# SplitUSB.net
KiCad netlist of a schematic drawn in EasyEDA Pro
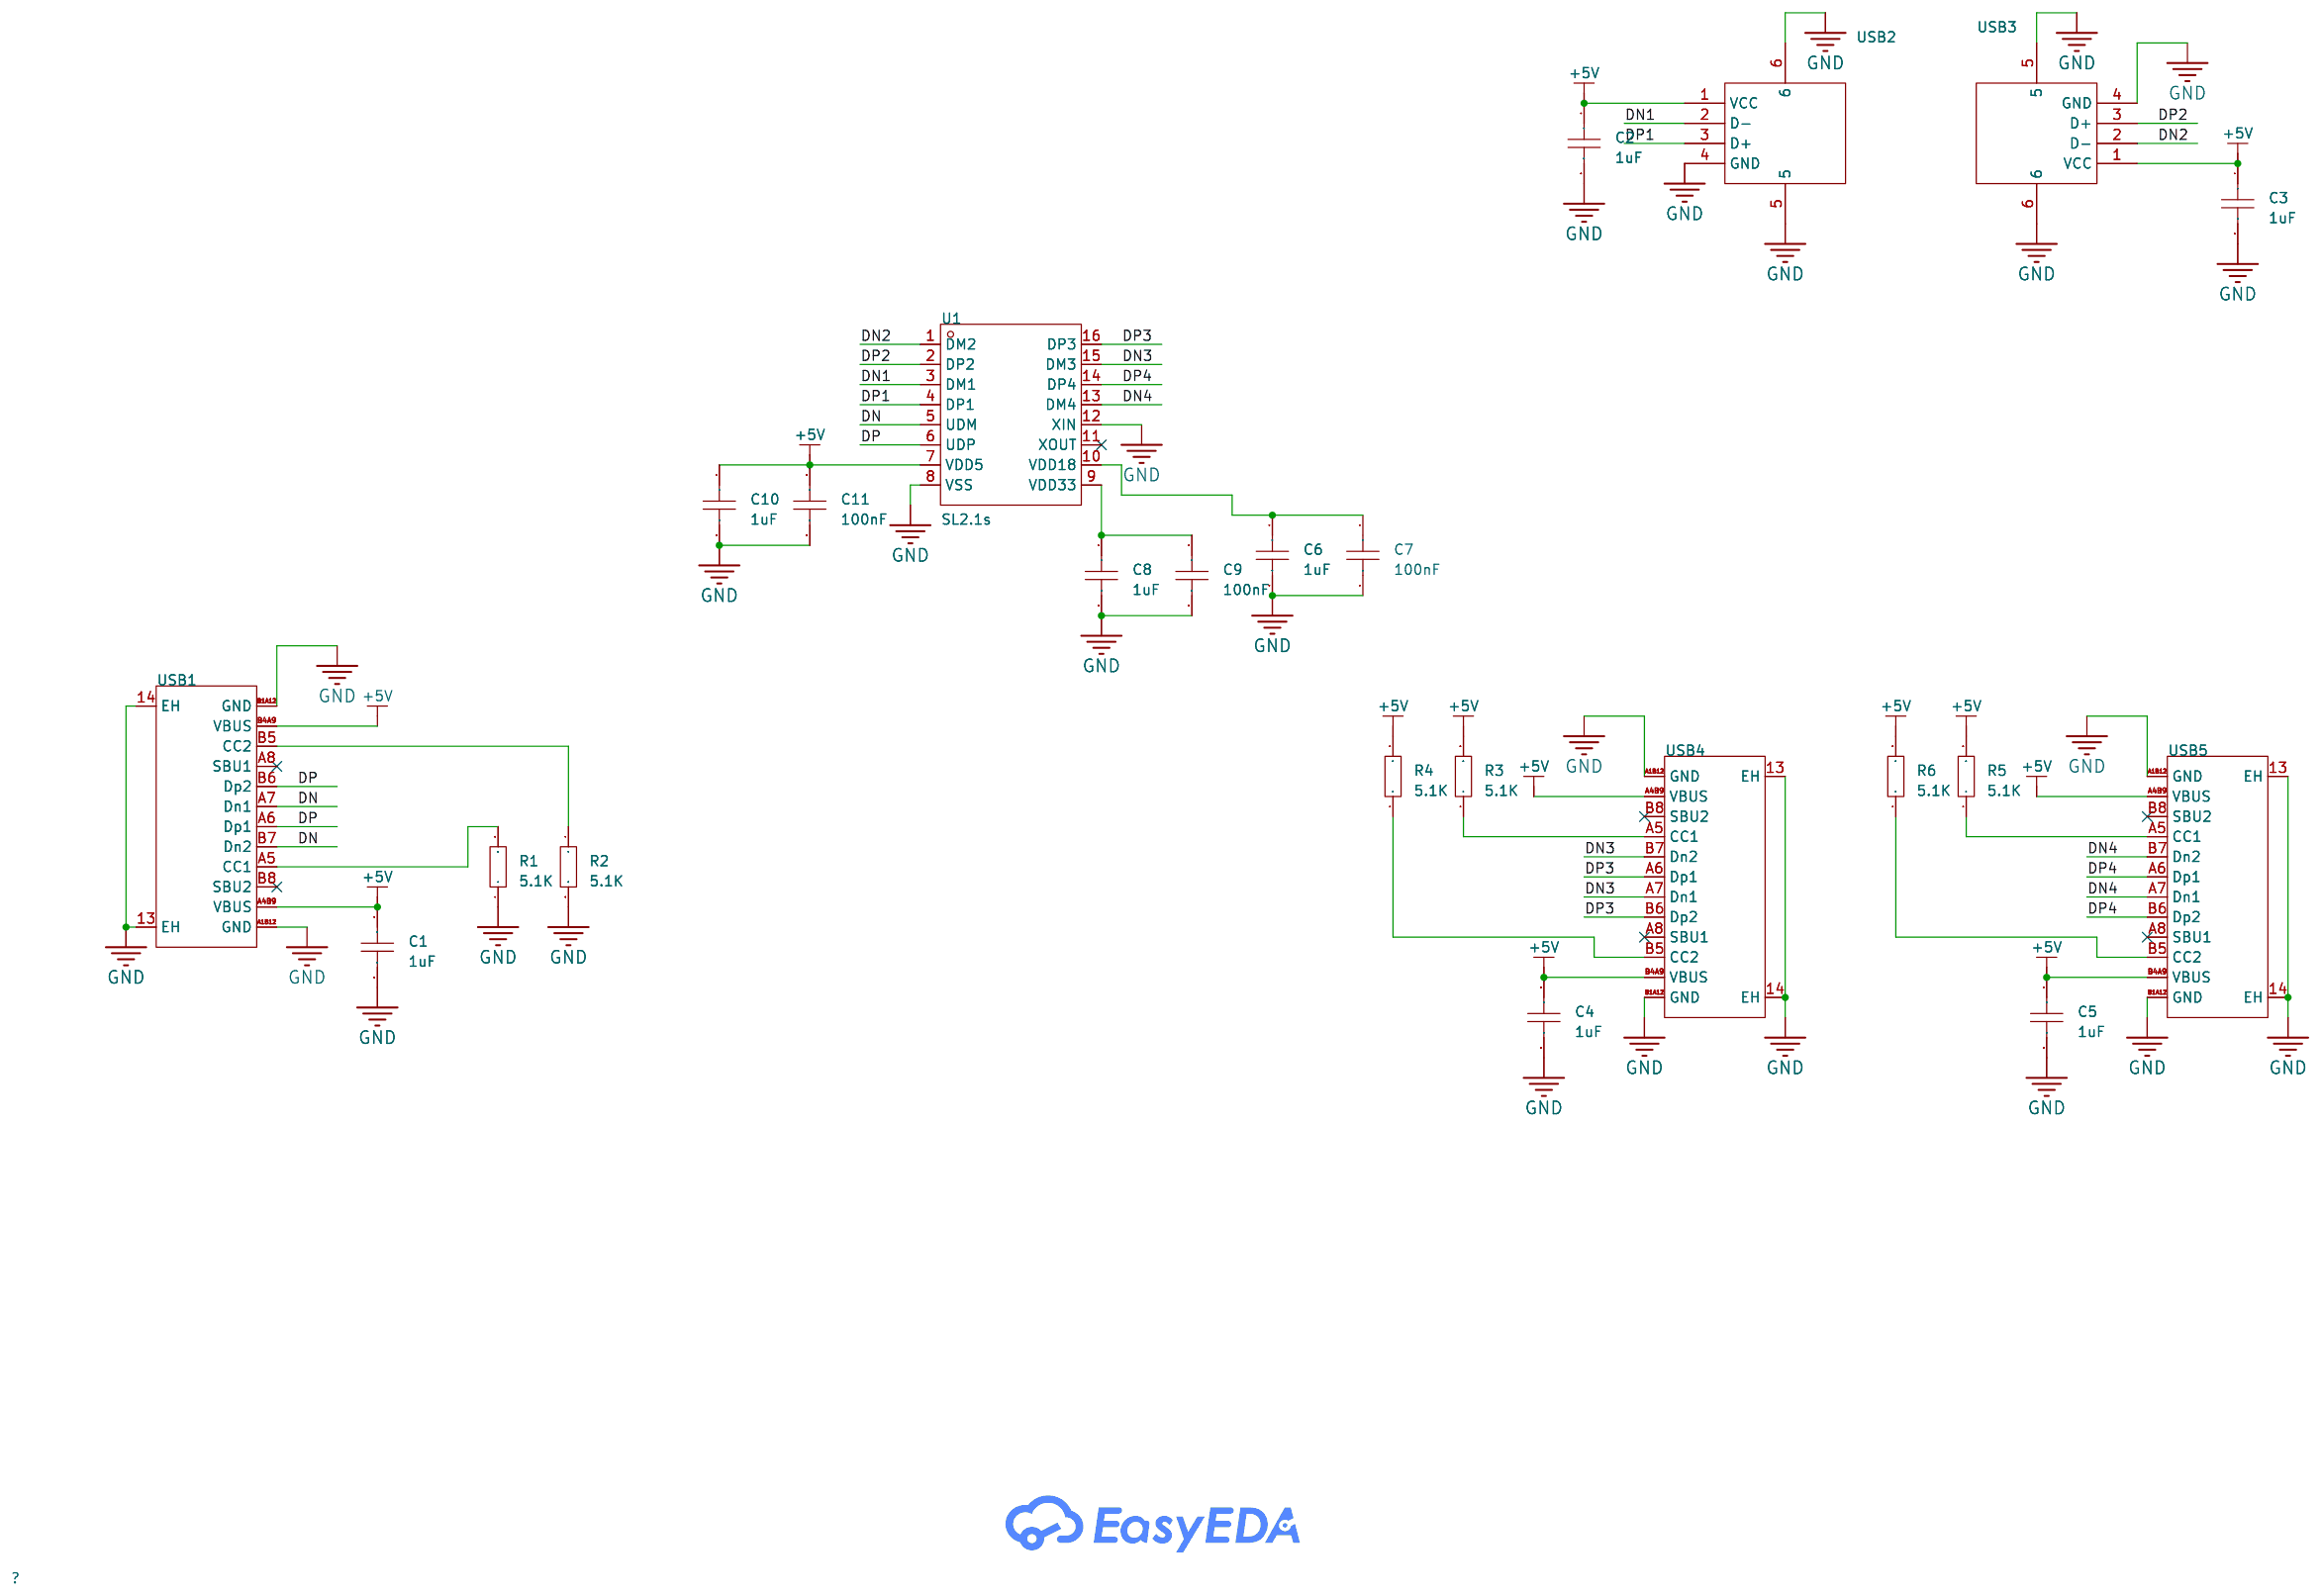
[diagram p0: schematic sheet]

(export (version "E")
  (design (tool "Eeschema 10.0.6"))
  (components
    (comp (ref "C1") (value "1uF") (footprint "easyedapro:C0603") (libsource (lib "easyedapro") (part "CAP")))
    (comp (ref "C2") (value "1uF") (footprint "easyedapro:C0603") (libsource (lib "easyedapro") (part "CAP")))
    (comp (ref "C3") (value "1uF") (footprint "easyedapro:C0603") (libsource (lib "easyedapro") (part "CAP")))
    (comp (ref "C4") (value "1uF") (footprint "easyedapro:C0603") (libsource (lib "easyedapro") (part "CAP")))
    (comp (ref "C5") (value "1uF") (footprint "easyedapro:C0603") (libsource (lib "easyedapro") (part "CAP")))
    (comp (ref "C6") (value "1uF") (footprint "easyedapro:C0603") (libsource (lib "easyedapro") (part "CAP")))
    (comp (ref "C7")
      (value "100nF")
      (footprint "easyedapro:C0603")
      (libsource (lib "easyedapro") (part "CAP"))
    )
    (comp (ref "C8") (value "1uF") (footprint "easyedapro:C0603") (libsource (lib "easyedapro") (part "CAP")))
    (comp (ref "C9")
      (value "100nF")
      (footprint "easyedapro:C0603")
      (libsource (lib "easyedapro") (part "CAP"))
    )
    (comp (ref "C10")
      (value "1uF")
      (footprint "easyedapro:C0603")
      (libsource (lib "easyedapro") (part "CAP"))
    )
    (comp (ref "C11")
      (value "100nF")
      (footprint "easyedapro:C0603")
      (libsource (lib "easyedapro") (part "CAP"))
    )
    (comp (ref "R1")
      (value "5.1K")
      (footprint "easyedapro:R0603")
      (libsource (lib "easyedapro") (part "Res"))
    )
    (comp (ref "R2")
      (value "5.1K")
      (footprint "easyedapro:R0603")
      (libsource (lib "easyedapro") (part "Res"))
    )
    (comp (ref "R3")
      (value "5.1K")
      (footprint "easyedapro:R0603")
      (libsource (lib "easyedapro") (part "Res"))
    )
    (comp (ref "R4")
      (value "5.1K")
      (footprint "easyedapro:R0603")
      (libsource (lib "easyedapro") (part "Res"))
    )
    (comp (ref "R5")
      (value "5.1K")
      (footprint "easyedapro:R0603")
      (libsource (lib "easyedapro") (part "Res"))
    )
    (comp (ref "R6")
      (value "5.1K")
      (footprint "easyedapro:R0603")
      (libsource (lib "easyedapro") (part "Res"))
    )
    (comp (ref "U1")
      (value "SL2.1s")
      (footprint "easyedapro:SSOP-16_L4.6-W2.6-P0.53-LS4.0-BL")
      (fields (field (name "Manufacturer") "CoreChips(和芯润德)"))
      (libsource (lib "easyedapro") (part "SL2.1S"))
    )
    (comp (ref "USB1")
      (value "TYPE-C 16PIN 2MD(073)")
      (footprint "easyedapro:USB-C-SMD_TYPE-C-16PIN-2MD-073")
      (fields (field (name "Manufacturer") "SHOU HAN(首韩)"))
      (libsource (lib "easyedapro") (part "TYPE-C 16PIN 2MD(073)"))
    )
    (comp (ref "USB2")
      (value "10.0 QHHTZB6.3")
      (footprint "easyedapro:USB-A-TH_10.0QHHTZB6.3")
      (fields (field (name "Manufacturer") "SHOU HAN(首韩)"))
      (libsource (lib "easyedapro") (part "10.0 QHHTZB6.3"))
    )
    (comp (ref "USB3")
      (value "10.0 QHHTZB6.3")
      (footprint "easyedapro:USB-A-TH_10.0QHHTZB6.3")
      (fields (field (name "Manufacturer") "SHOU HAN(首韩)"))
      (libsource (lib "easyedapro") (part "10.0 QHHTZB6.3"))
    )
    (comp (ref "USB4")
      (value "TYPE-C 16PIN 2MD(073)")
      (footprint "easyedapro:USB-C-SMD_TYPE-C-16PIN-2MD-073")
      (fields (field (name "Manufacturer") "SHOU HAN(首韩)"))
      (libsource (lib "easyedapro") (part "TYPE-C 16PIN 2MD(073)"))
    )
    (comp (ref "USB5")
      (value "TYPE-C 16PIN 2MD(073)")
      (footprint "easyedapro:USB-C-SMD_TYPE-C-16PIN-2MD-073")
      (fields (field (name "Manufacturer") "SHOU HAN(首韩)"))
      (libsource (lib "easyedapro") (part "TYPE-C 16PIN 2MD(073)"))
    )
  )
  (nets
    (net (code "1") (name "+5V") (class "Default")
      (node (ref "C1") (pin "1") (pinfunction "1_1") (pintype "input"))
      (node (ref "C10") (pin "1") (pinfunction "1_1") (pintype "input"))
      (node (ref "C11") (pin "1") (pinfunction "1_1") (pintype "input"))
      (node (ref "C2") (pin "1") (pinfunction "1_1") (pintype "input"))
      (node (ref "C3") (pin "1") (pinfunction "1_1") (pintype "input"))
      (node (ref "C4") (pin "1") (pinfunction "1_1") (pintype "input"))
      (node (ref "C5") (pin "1") (pinfunction "1_1") (pintype "input"))
      (node (ref "R3") (pin "2") (pinfunction "2_2") (pintype "input"))
      (node (ref "R4") (pin "2") (pinfunction "2_2") (pintype "input"))
      (node (ref "R5") (pin "2") (pinfunction "2_2") (pintype "input"))
      (node (ref "R6") (pin "2") (pinfunction "2_2") (pintype "input"))
      (node (ref "U1") (pin "7") (pinfunction "VDD5_7") (pintype "unspecified"))
      (node (ref "USB1") (pin "A4B9") (pinfunction "VBUS_A4B9") (pintype "unspecified"))
      (node (ref "USB1") (pin "B4A9") (pinfunction "VBUS_B4A9") (pintype "unspecified"))
      (node (ref "USB2") (pin "1") (pinfunction "VCC_1") (pintype "unspecified"))
      (node (ref "USB3") (pin "1") (pinfunction "VCC_1") (pintype "unspecified"))
      (node (ref "USB4") (pin "A4B9") (pinfunction "VBUS_A4B9") (pintype "unspecified"))
      (node (ref "USB4") (pin "B4A9") (pinfunction "VBUS_B4A9") (pintype "unspecified"))
      (node (ref "USB5") (pin "A4B9") (pinfunction "VBUS_A4B9") (pintype "unspecified"))
      (node (ref "USB5") (pin "B4A9") (pinfunction "VBUS_B4A9") (pintype "unspecified"))
    )
    (net (code "2") (name "/DN") (class "Default")
      (node (ref "U1") (pin "5") (pinfunction "UDM_5") (pintype "unspecified"))
      (node (ref "USB1") (pin "A7") (pinfunction "Dn1_A7") (pintype "unspecified"))
      (node (ref "USB1") (pin "B7") (pinfunction "Dn2_B7") (pintype "unspecified"))
    )
    (net (code "3") (name "/DN1") (class "Default")
      (node (ref "U1") (pin "3") (pinfunction "DM1_3") (pintype "unspecified"))
      (node (ref "USB2") (pin "2") (pinfunction "D-_2") (pintype "unspecified"))
    )
    (net (code "4") (name "/DN2") (class "Default")
      (node (ref "U1") (pin "1") (pinfunction "DM2_1") (pintype "unspecified"))
      (node (ref "USB3") (pin "2") (pinfunction "D-_2") (pintype "unspecified"))
    )
    (net (code "5") (name "/DN3") (class "Default")
      (node (ref "U1") (pin "15") (pinfunction "DM3_15") (pintype "unspecified"))
      (node (ref "USB4") (pin "A7") (pinfunction "Dn1_A7") (pintype "unspecified"))
      (node (ref "USB4") (pin "B7") (pinfunction "Dn2_B7") (pintype "unspecified"))
    )
    (net (code "6") (name "/DN4") (class "Default")
      (node (ref "U1") (pin "13") (pinfunction "DM4_13") (pintype "unspecified"))
      (node (ref "USB5") (pin "A7") (pinfunction "Dn1_A7") (pintype "unspecified"))
      (node (ref "USB5") (pin "B7") (pinfunction "Dn2_B7") (pintype "unspecified"))
    )
    (net (code "7") (name "/DP") (class "Default")
      (node (ref "U1") (pin "6") (pinfunction "UDP_6") (pintype "unspecified"))
      (node (ref "USB1") (pin "A6") (pinfunction "Dp1_A6") (pintype "unspecified"))
      (node (ref "USB1") (pin "B6") (pinfunction "Dp2_B6") (pintype "unspecified"))
    )
    (net (code "8") (name "/DP1") (class "Default")
      (node (ref "U1") (pin "4") (pinfunction "DP1_4") (pintype "unspecified"))
      (node (ref "USB2") (pin "3") (pinfunction "D+_3") (pintype "unspecified"))
    )
    (net (code "9") (name "/DP2") (class "Default")
      (node (ref "U1") (pin "2") (pinfunction "DP2_2") (pintype "unspecified"))
      (node (ref "USB3") (pin "3") (pinfunction "D+_3") (pintype "unspecified"))
    )
    (net (code "10") (name "/DP3") (class "Default")
      (node (ref "U1") (pin "16") (pinfunction "DP3_16") (pintype "unspecified"))
      (node (ref "USB4") (pin "A6") (pinfunction "Dp1_A6") (pintype "unspecified"))
      (node (ref "USB4") (pin "B6") (pinfunction "Dp2_B6") (pintype "unspecified"))
    )
    (net (code "11") (name "/DP4") (class "Default")
      (node (ref "U1") (pin "14") (pinfunction "DP4_14") (pintype "unspecified"))
      (node (ref "USB5") (pin "A6") (pinfunction "Dp1_A6") (pintype "unspecified"))
      (node (ref "USB5") (pin "B6") (pinfunction "Dp2_B6") (pintype "unspecified"))
    )
    (net (code "12") (name "GND") (class "Default")
      (node (ref "C1") (pin "2") (pinfunction "2_2") (pintype "input"))
      (node (ref "C10") (pin "2") (pinfunction "2_2") (pintype "input"))
      (node (ref "C11") (pin "2") (pinfunction "2_2") (pintype "input"))
      (node (ref "C2") (pin "2") (pinfunction "2_2") (pintype "input"))
      (node (ref "C3") (pin "2") (pinfunction "2_2") (pintype "input"))
      (node (ref "C4") (pin "2") (pinfunction "2_2") (pintype "input"))
      (node (ref "C5") (pin "2") (pinfunction "2_2") (pintype "input"))
      (node (ref "C6") (pin "2") (pinfunction "2_2") (pintype "input"))
      (node (ref "C7") (pin "2") (pinfunction "2_2") (pintype "input"))
      (node (ref "C8") (pin "2") (pinfunction "2_2") (pintype "input"))
      (node (ref "C9") (pin "2") (pinfunction "2_2") (pintype "input"))
      (node (ref "R1") (pin "1") (pinfunction "1_1") (pintype "input"))
      (node (ref "R2") (pin "2") (pinfunction "2_2") (pintype "input"))
      (node (ref "U1") (pin "12") (pinfunction "XIN_12") (pintype "unspecified"))
      (node (ref "U1") (pin "8") (pinfunction "VSS_8") (pintype "unspecified"))
      (node (ref "USB1") (pin "13") (pinfunction "EH_13") (pintype "unspecified"))
      (node (ref "USB1") (pin "14") (pinfunction "EH_14") (pintype "unspecified"))
      (node (ref "USB1") (pin "A1B12") (pinfunction "GND_A1B12") (pintype "unspecified"))
      (node (ref "USB1") (pin "B1A12") (pinfunction "GND_B1A12") (pintype "unspecified"))
      (node (ref "USB2") (pin "4") (pinfunction "GND_4") (pintype "unspecified"))
      (node (ref "USB2") (pin "5") (pinfunction "5_5") (pintype "unspecified"))
      (node (ref "USB2") (pin "6") (pinfunction "6_6") (pintype "unspecified"))
      (node (ref "USB3") (pin "4") (pinfunction "GND_4") (pintype "unspecified"))
      (node (ref "USB3") (pin "5") (pinfunction "5_5") (pintype "unspecified"))
      (node (ref "USB3") (pin "6") (pinfunction "6_6") (pintype "unspecified"))
      (node (ref "USB4") (pin "13") (pinfunction "EH_13") (pintype "unspecified"))
      (node (ref "USB4") (pin "14") (pinfunction "EH_14") (pintype "unspecified"))
      (node (ref "USB4") (pin "A1B12") (pinfunction "GND_A1B12") (pintype "unspecified"))
      (node (ref "USB4") (pin "B1A12") (pinfunction "GND_B1A12") (pintype "unspecified"))
      (node (ref "USB5") (pin "13") (pinfunction "EH_13") (pintype "unspecified"))
      (node (ref "USB5") (pin "14") (pinfunction "EH_14") (pintype "unspecified"))
      (node (ref "USB5") (pin "A1B12") (pinfunction "GND_A1B12") (pintype "unspecified"))
      (node (ref "USB5") (pin "B1A12") (pinfunction "GND_B1A12") (pintype "unspecified"))
    )
    (net (code "13") (name "Net-(U1-VDD18)") (class "Default")
      (node (ref "C6") (pin "1") (pinfunction "1_1") (pintype "input"))
      (node (ref "C7") (pin "1") (pinfunction "1_1") (pintype "input"))
      (node (ref "U1") (pin "10") (pinfunction "VDD18_10") (pintype "unspecified"))
    )
    (net (code "14") (name "Net-(U1-VDD33)") (class "Default")
      (node (ref "C8") (pin "1") (pinfunction "1_1") (pintype "input"))
      (node (ref "C9") (pin "1") (pinfunction "1_1") (pintype "input"))
      (node (ref "U1") (pin "9") (pinfunction "VDD33_9") (pintype "unspecified"))
    )
    (net (code "15") (name "Net-(USB1-CC1)") (class "Default")
      (node (ref "R1") (pin "2") (pinfunction "2_2") (pintype "input"))
      (node (ref "USB1") (pin "A5") (pinfunction "CC1_A5") (pintype "unspecified"))
    )
    (net (code "16") (name "Net-(USB1-CC2)") (class "Default")
      (node (ref "R2") (pin "1") (pinfunction "1_1") (pintype "input"))
      (node (ref "USB1") (pin "B5") (pinfunction "CC2_B5") (pintype "unspecified"))
    )
    (net (code "17") (name "Net-(USB4-CC1)") (class "Default")
      (node (ref "R3") (pin "1") (pinfunction "1_1") (pintype "input"))
      (node (ref "USB4") (pin "A5") (pinfunction "CC1_A5") (pintype "unspecified"))
    )
    (net (code "18") (name "Net-(USB4-CC2)") (class "Default")
      (node (ref "R4") (pin "1") (pinfunction "1_1") (pintype "input"))
      (node (ref "USB4") (pin "B5") (pinfunction "CC2_B5") (pintype "unspecified"))
    )
    (net (code "19") (name "Net-(USB5-CC1)") (class "Default")
      (node (ref "R5") (pin "1") (pinfunction "1_1") (pintype "input"))
      (node (ref "USB5") (pin "A5") (pinfunction "CC1_A5") (pintype "unspecified"))
    )
    (net (code "20") (name "Net-(USB5-CC2)") (class "Default")
      (node (ref "R6") (pin "1") (pinfunction "1_1") (pintype "input"))
      (node (ref "USB5") (pin "B5") (pinfunction "CC2_B5") (pintype "unspecified"))
    )
    (net (code "21") (name "unconnected-(U1-XOUT-Pad11)") (class "Default")
      (node (ref "U1") (pin "11") (pinfunction "XOUT_11") (pintype "unspecified+no_connect"))
    )
    (net (code "22") (name "unconnected-(USB1-SBU1-PadA8)") (class "Default")
      (node (ref "USB1") (pin "A8") (pinfunction "SBU1_A8") (pintype "unspecified+no_connect"))
    )
    (net (code "23") (name "unconnected-(USB1-SBU2-PadB8)") (class "Default")
      (node (ref "USB1") (pin "B8") (pinfunction "SBU2_B8") (pintype "unspecified+no_connect"))
    )
    (net (code "24") (name "unconnected-(USB4-SBU1-PadA8)") (class "Default")
      (node (ref "USB4") (pin "A8") (pinfunction "SBU1_A8") (pintype "unspecified+no_connect"))
    )
    (net (code "25") (name "unconnected-(USB4-SBU2-PadB8)") (class "Default")
      (node (ref "USB4") (pin "B8") (pinfunction "SBU2_B8") (pintype "unspecified+no_connect"))
    )
    (net (code "26") (name "unconnected-(USB5-SBU1-PadA8)") (class "Default")
      (node (ref "USB5") (pin "A8") (pinfunction "SBU1_A8") (pintype "unspecified+no_connect"))
    )
    (net (code "27") (name "unconnected-(USB5-SBU2-PadB8)") (class "Default")
      (node (ref "USB5") (pin "B8") (pinfunction "SBU2_B8") (pintype "unspecified+no_connect"))
    )
  )
)
